# shield.net
KiCad netlist of a schematic drawn in EAGLE
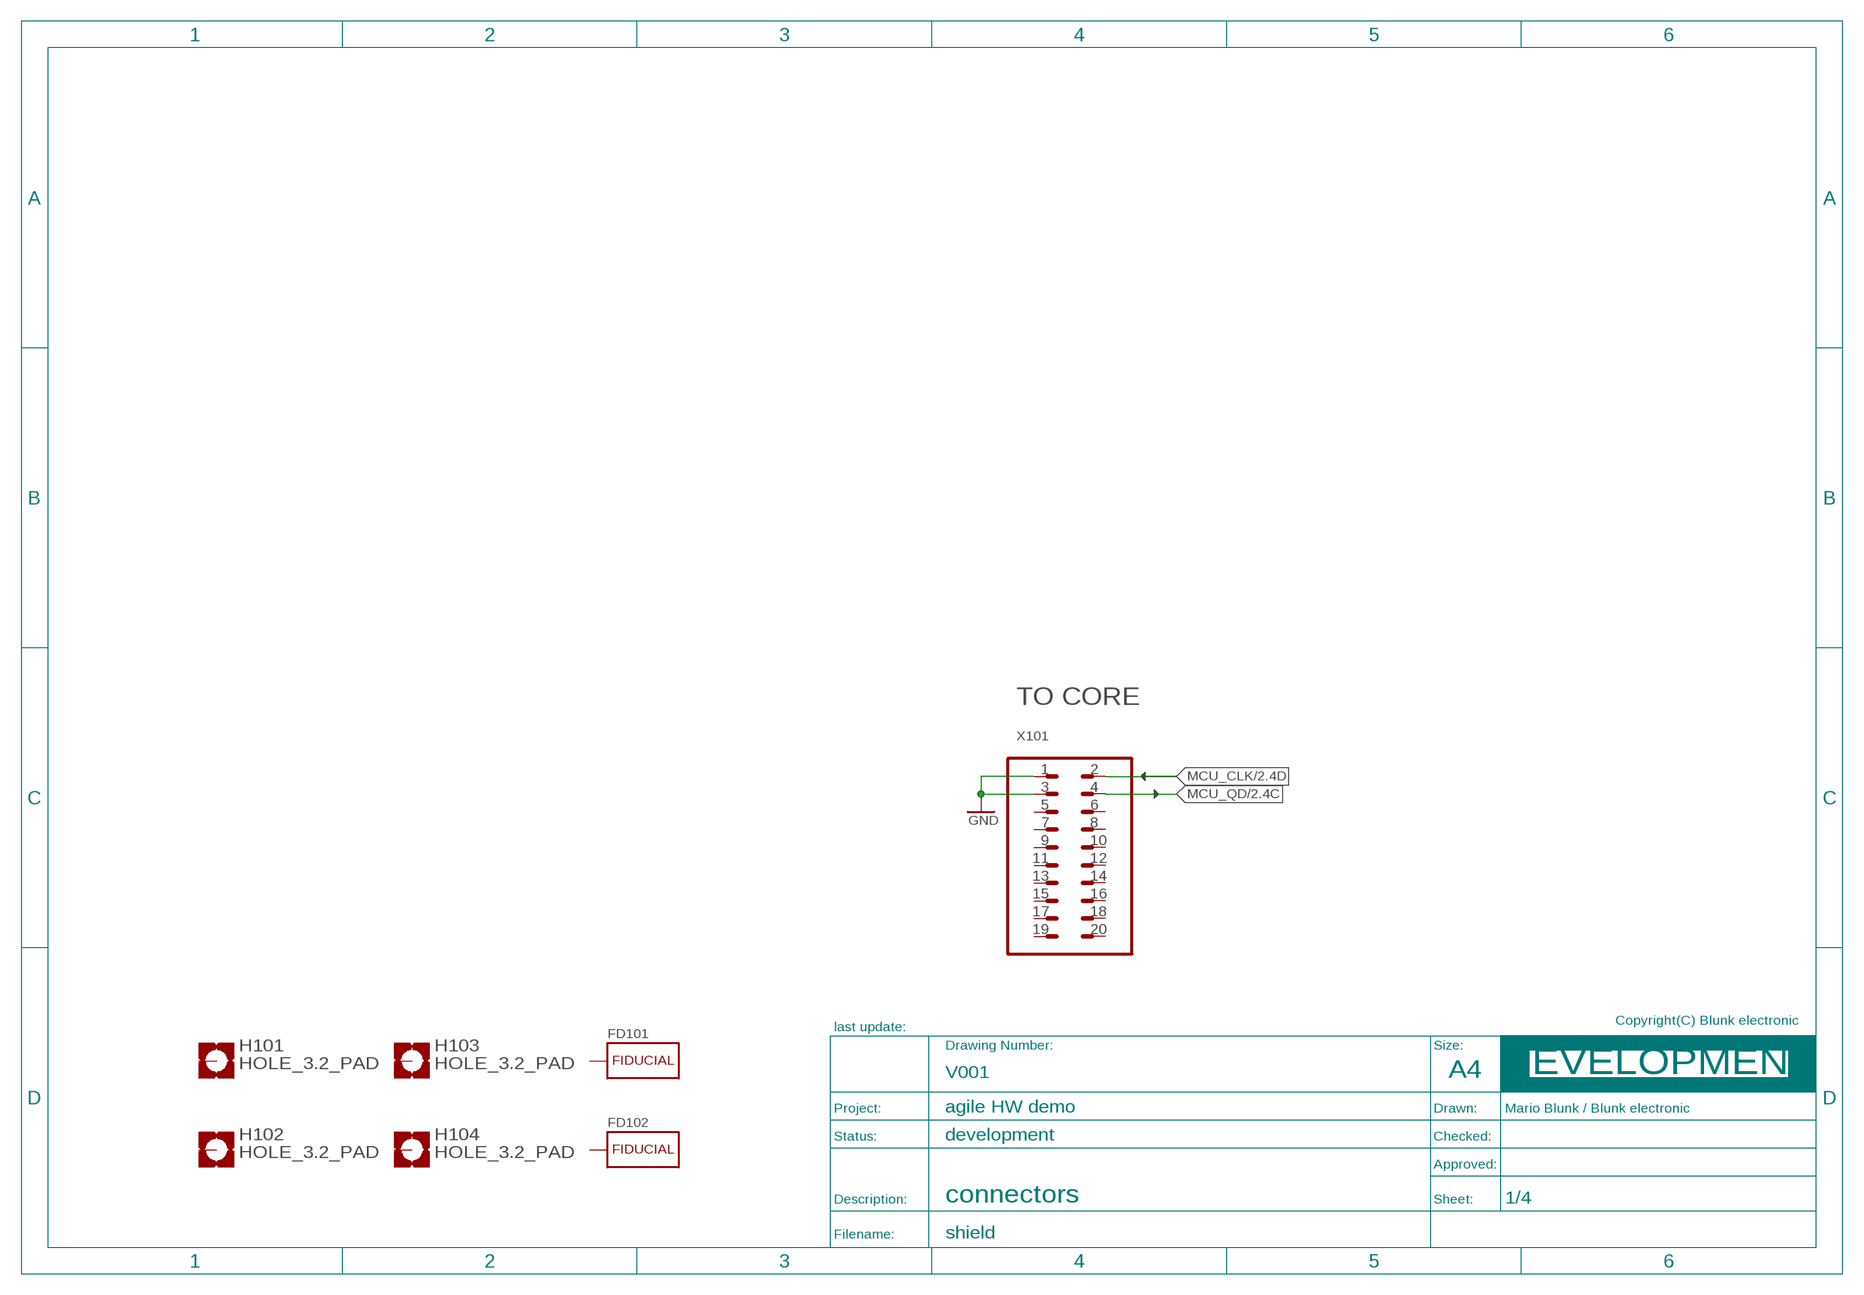
[diagram p0: schematic, sheet 1]
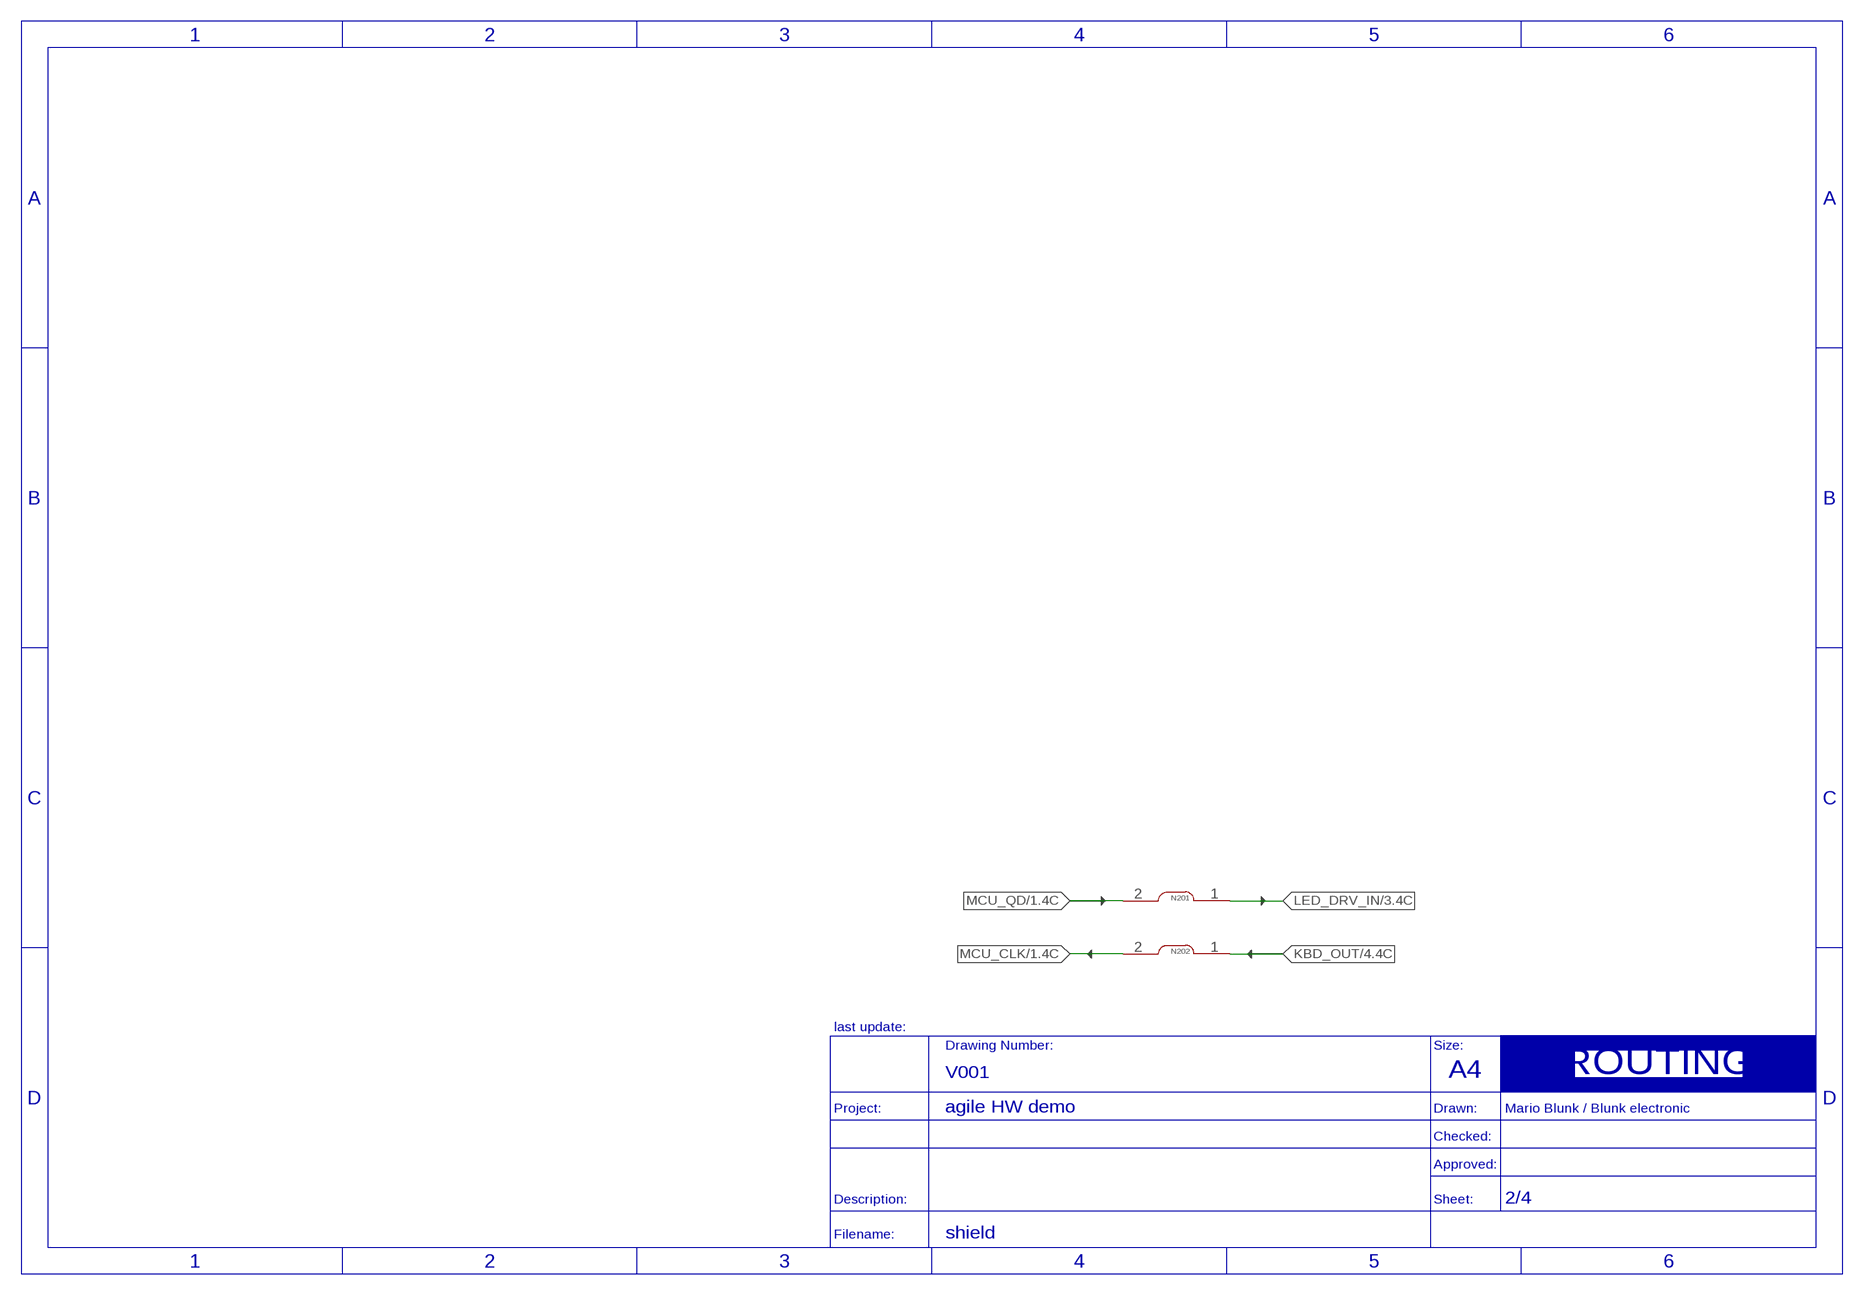
[diagram p1: schematic, sheet 2]
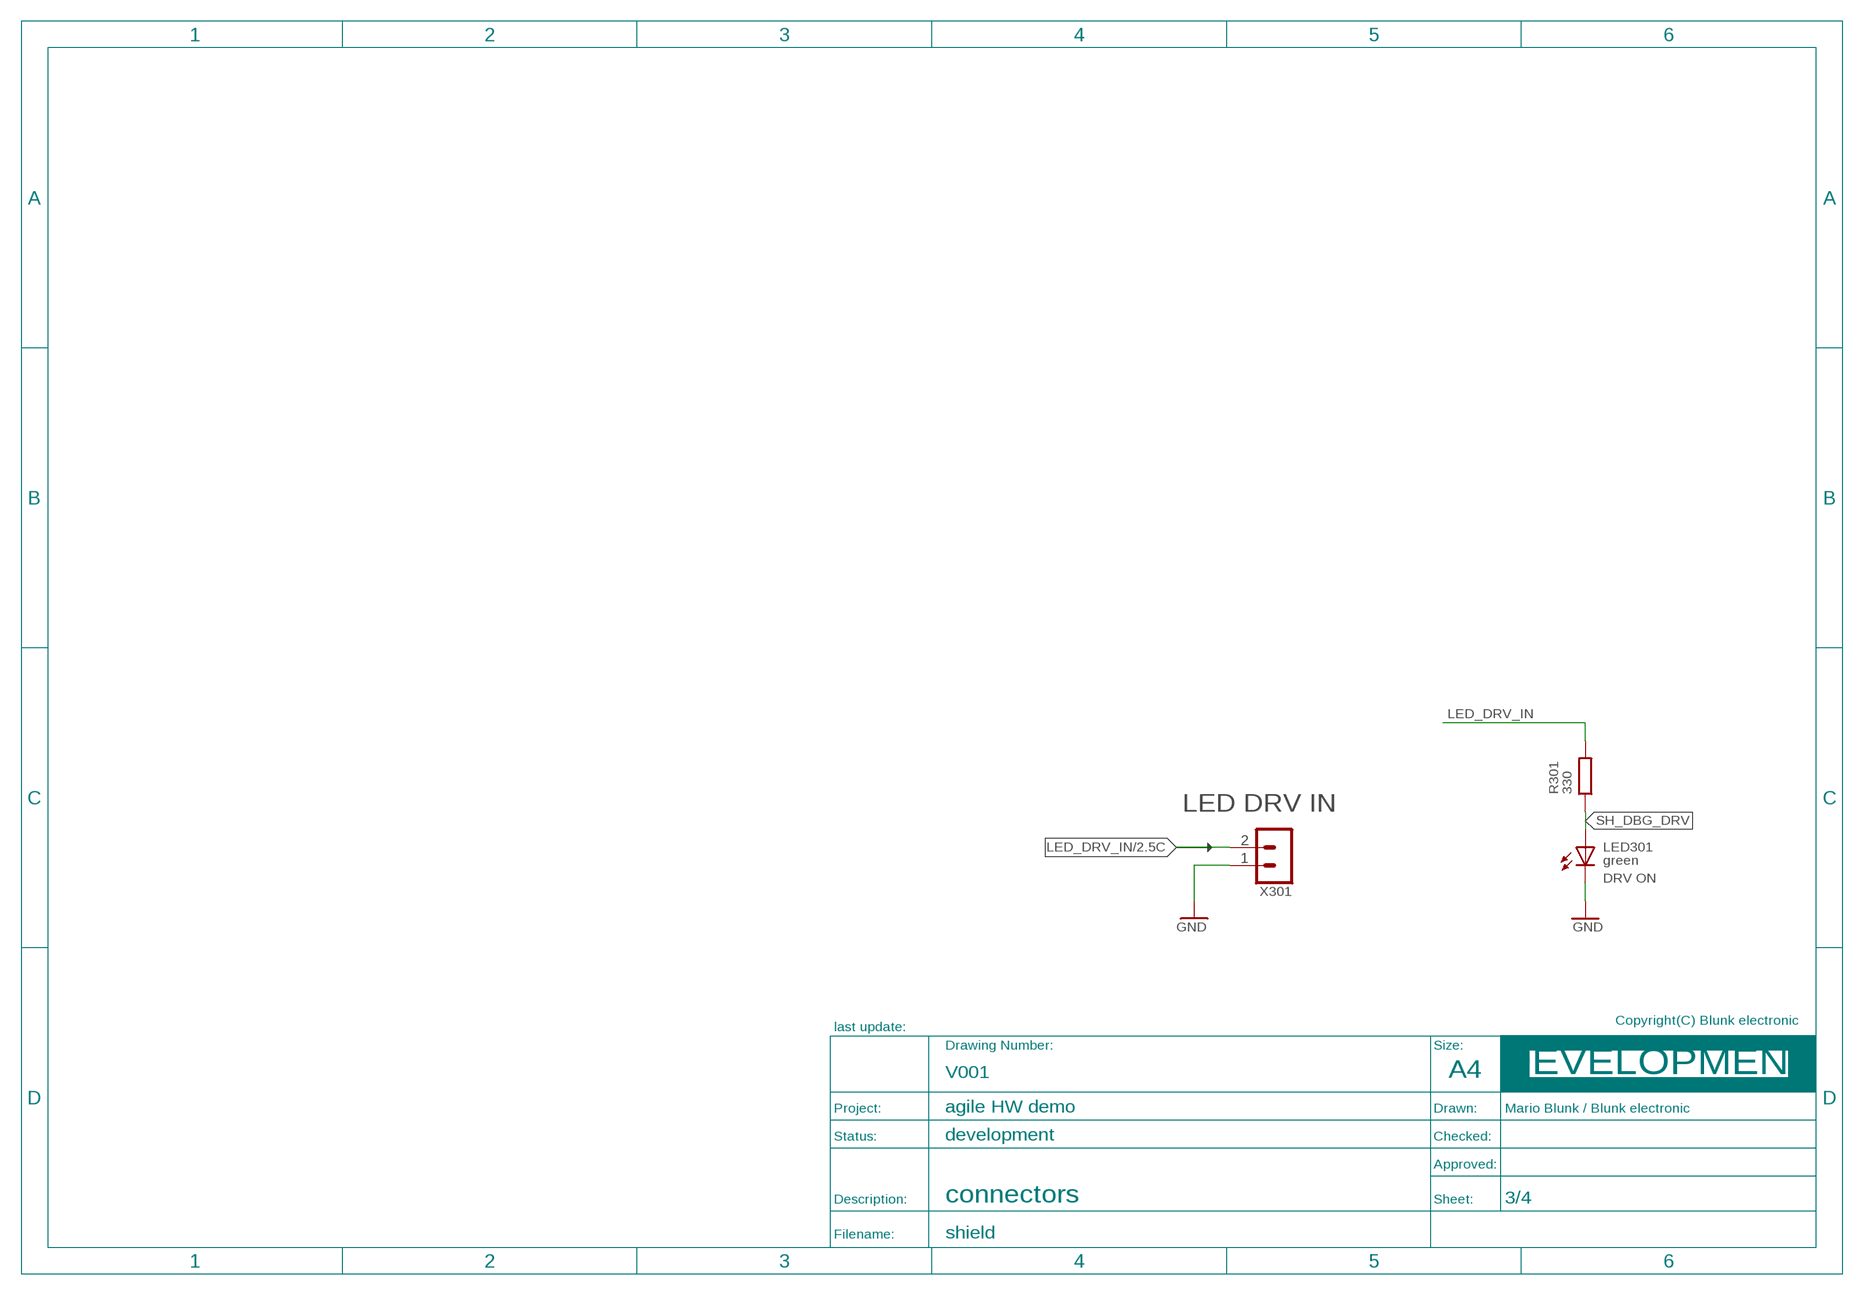
[diagram p2: schematic, sheet 3]
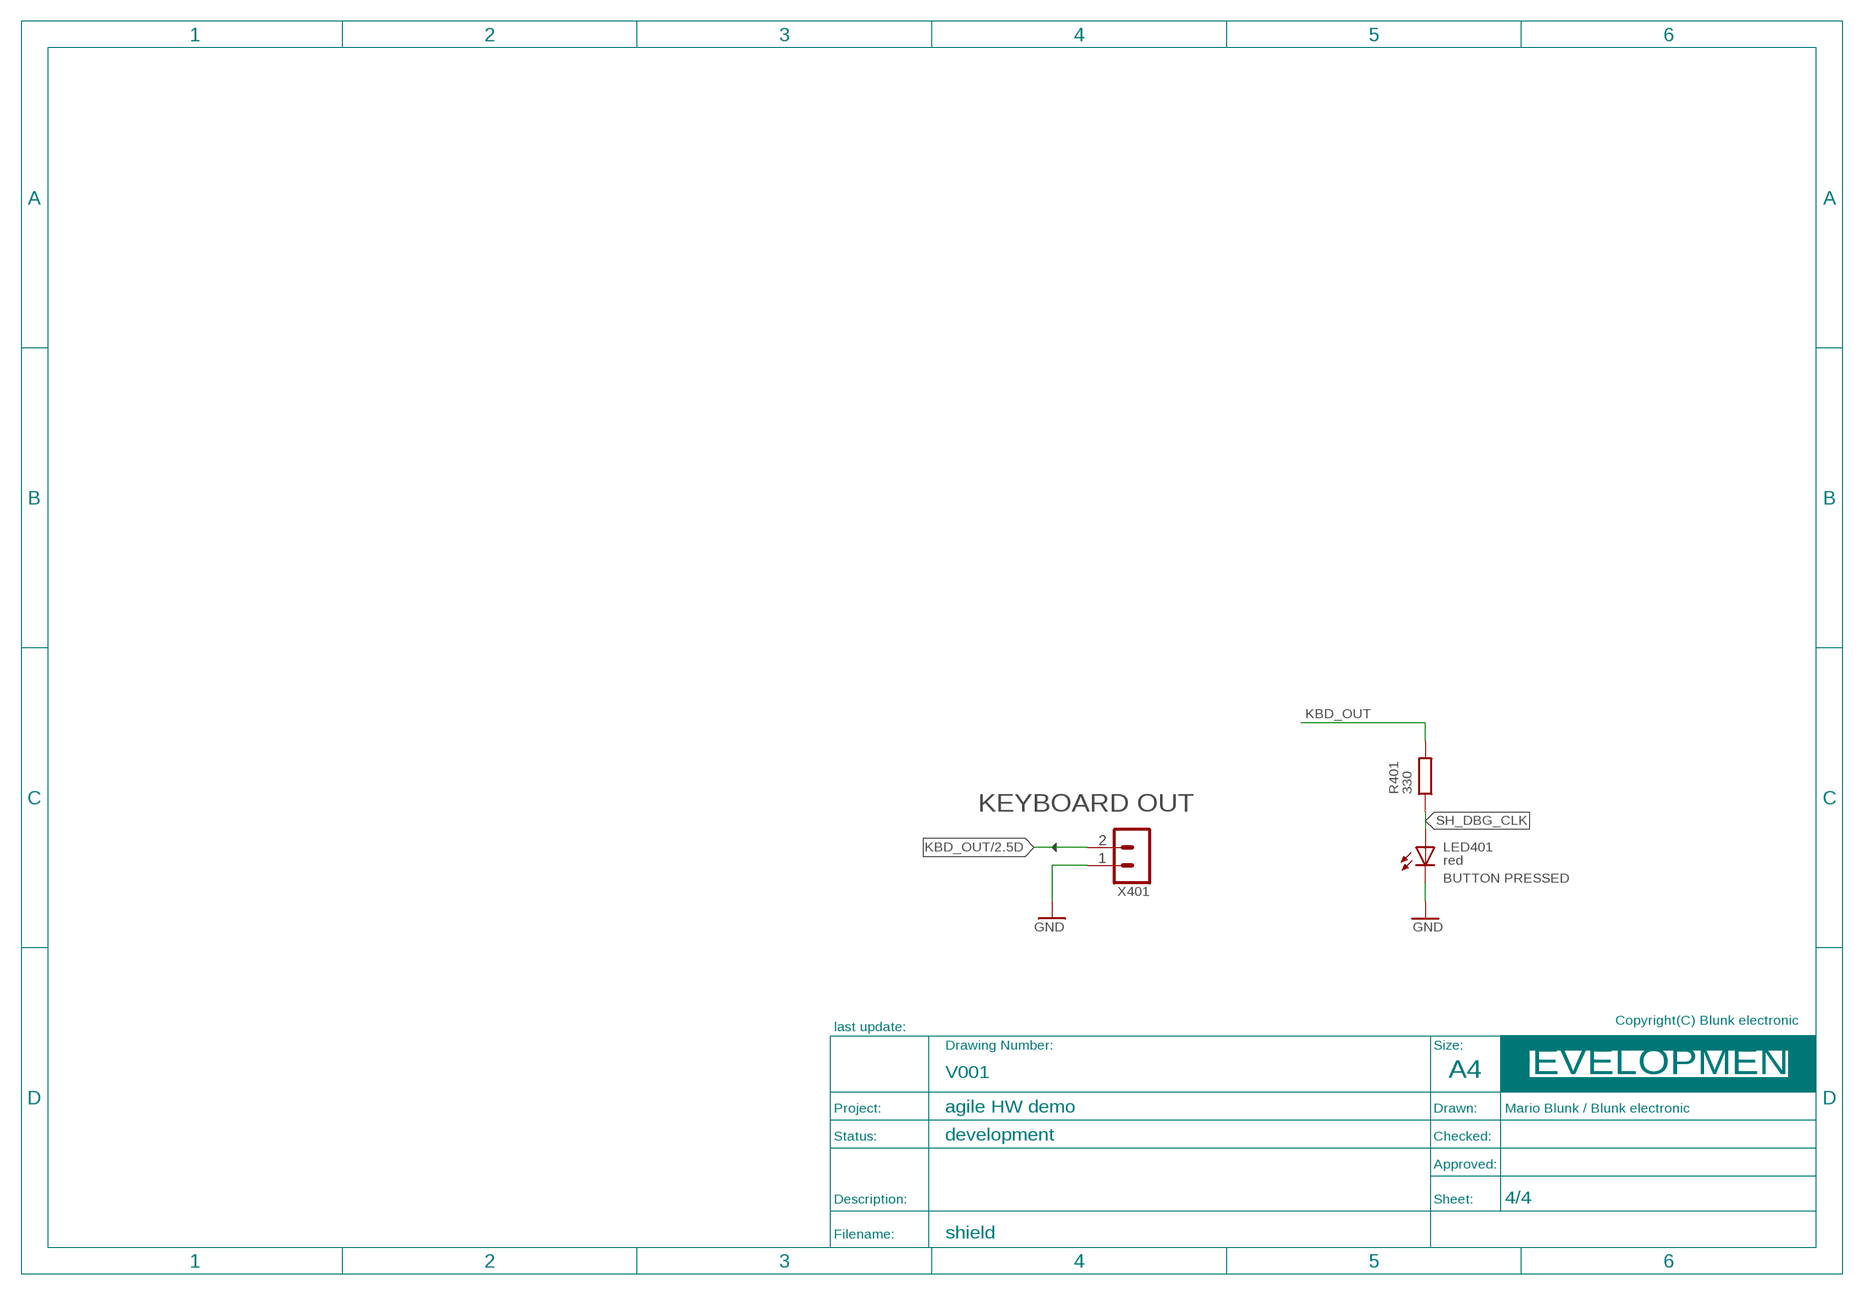
[diagram p3: schematic, sheet 4]

(export (version "E")
  (design (tool "Eeschema 10.0.6"))
  (components
    (comp (ref "N201")
      (value "NET_CHANGER-S-0.3MM")
      (footprint "eagle-import:S_NET_CHANGER_0.3MM")
      (libsource (lib "eagle-import") (part "NET_CHANGER-S-0.3MM"))
    )
    (comp (ref "N202")
      (value "NET_CHANGER-S-0.15MM")
      (footprint "eagle-import:S_NET_CHANGER_0.15MM")
      (libsource (lib "eagle-import") (part "NET_CHANGER-S-0.15MM"))
    )
    (comp (ref "LED301")
      (value "green")
      (footprint "eagle-import:S_0805")
      (fields (field (name "FUNCTION") "DRV ON") (field (name "PART_CODE_BEL") "LED_PAC_S_0805_VAL_green"))
      (libsource (lib "eagle-import") (part "LED_S_0805"))
    )
    (comp (ref "R301")
      (value "330")
      (footprint "eagle-import:S_0805")
      (fields (field (name "PART_CODE_BEL") "R_PAC_S_0805_VAL_330"))
      (libsource (lib "eagle-import") (part "R_S_0805"))
    )
    (comp (ref "X301")
      (value "MALE_2X1-T-VERTICAL")
      (footprint "eagle-import:T_MALE_2X1_VERTICAL_PITCH_2MM54")
      (fields (field (name "FUNCTION") "LED DRV IN"))
      (libsource (lib "eagle-import") (part "MALE_2X1-T-VERTICAL"))
    )
    (comp (ref "FD101")
      (value "FIDUCIAL_CROSSHAIR")
      (footprint "eagle-import:CROSSHAIR")
      (libsource (lib "eagle-import") (part "FIDUCIAL_CROSSHAIR"))
    )
    (comp (ref "FD102")
      (value "FIDUCIAL_CROSSHAIR")
      (footprint "eagle-import:CROSSHAIR")
      (libsource (lib "eagle-import") (part "FIDUCIAL_CROSSHAIR"))
    )
    (comp (ref "H101")
      (value "HOLE_3.2_PAD")
      (footprint "eagle-import:3.2_PAD")
      (libsource (lib "eagle-import") (part "HOLE_3.2_PAD"))
    )
    (comp (ref "H102")
      (value "HOLE_3.2_PAD")
      (footprint "eagle-import:3.2_PAD")
      (libsource (lib "eagle-import") (part "HOLE_3.2_PAD"))
    )
    (comp (ref "H103")
      (value "HOLE_3.2_PAD")
      (footprint "eagle-import:3.2_PAD")
      (libsource (lib "eagle-import") (part "HOLE_3.2_PAD"))
    )
    (comp (ref "H104")
      (value "HOLE_3.2_PAD")
      (footprint "eagle-import:3.2_PAD")
      (libsource (lib "eagle-import") (part "HOLE_3.2_PAD"))
    )
    (comp (ref "X101")
      (value "MALE_2X10-T-VERTICAL_2.54MM")
      (footprint "eagle-import:T_MALE_2X10_VERTICAL_GRID_2.54MM")
      (fields
        (field (name "FUNCTION") "TO CORE")
        (field (name "PART_CODE_BEL") "X_PAC_T_MALE_2X10_VERTICAL_PITCH_2mm54")
      )
      (libsource (lib "eagle-import") (part "MALE_2X10-T-VERTICAL_2.54MM"))
    )
    (comp (ref "LED401")
      (value "red")
      (footprint "eagle-import:S_0805")
      (fields
        (field (name "FUNCTION") "BUTTON PRESSED")
        (field (name "PART_CODE_BEL") "LED_PAC_S_0805_VAL_red")
      )
      (libsource (lib "eagle-import") (part "LED_S_0805"))
    )
    (comp (ref "R401")
      (value "330")
      (footprint "eagle-import:S_0805")
      (fields (field (name "PART_CODE_BEL") "R_PAC_S_0805_VAL_330"))
      (libsource (lib "eagle-import") (part "R_S_0805"))
    )
    (comp (ref "X401")
      (value "MALE_2X1-T-VERTICAL")
      (footprint "eagle-import:T_MALE_2X1_VERTICAL_PITCH_2MM54")
      (fields (field (name "FUNCTION") "KEYBOARD OUT"))
      (libsource (lib "eagle-import") (part "MALE_2X1-T-VERTICAL"))
    )
  )
  (nets
    (net (code "1") (name "GND") (class "Default")
      (node (ref "LED301") (pin "C") (pinfunction "C_C") (pintype "passive"))
      (node (ref "LED401") (pin "C") (pinfunction "C_C") (pintype "passive"))
      (node (ref "X101") (pin "1") (pinfunction "1_1") (pintype "passive"))
      (node (ref "X101") (pin "3") (pinfunction "3_3") (pintype "passive"))
      (node (ref "X301") (pin "1") (pinfunction "1_1") (pintype "passive"))
      (node (ref "X401") (pin "1") (pinfunction "1_1") (pintype "passive"))
    )
    (net (code "2") (name "KBD_OUT") (class "Default")
      (node (ref "N202") (pin "1") (pinfunction "1_1") (pintype "passive"))
      (node (ref "R401") (pin "2") (pinfunction "2_2") (pintype "passive"))
      (node (ref "X401") (pin "2") (pinfunction "2_2") (pintype "passive"))
    )
    (net (code "3") (name "LED_DRV_IN") (class "Default")
      (node (ref "N201") (pin "1") (pinfunction "1_1") (pintype "passive"))
      (node (ref "R301") (pin "2") (pinfunction "2_2") (pintype "passive"))
      (node (ref "X301") (pin "2") (pinfunction "2_2") (pintype "passive"))
    )
    (net (code "4") (name "MCU_CLK") (class "Default")
      (node (ref "N202") (pin "2") (pinfunction "2_2") (pintype "passive"))
      (node (ref "X101") (pin "2") (pinfunction "2_2") (pintype "passive"))
    )
    (net (code "5") (name "MCU_QD") (class "Default")
      (node (ref "N201") (pin "2") (pinfunction "2_2") (pintype "passive"))
      (node (ref "X101") (pin "4") (pinfunction "4_4") (pintype "passive"))
    )
    (net (code "6") (name "SH_DBG_CLK") (class "Default")
      (node (ref "LED401") (pin "A") (pinfunction "A_A") (pintype "passive"))
      (node (ref "R401") (pin "1") (pinfunction "1_1") (pintype "passive"))
    )
    (net (code "7") (name "SH_DBG_DRV") (class "Default")
      (node (ref "LED301") (pin "A") (pinfunction "A_A") (pintype "passive"))
      (node (ref "R301") (pin "1") (pinfunction "1_1") (pintype "passive"))
    )
    (net (code "8") (name "unconnected-(FD101-NC-Pad1)") (class "Default")
      (node (ref "FD101") (pin "1") (pinfunction "NC_1") (pintype "no_connect"))
    )
    (net (code "9") (name "unconnected-(FD102-NC-Pad1)") (class "Default")
      (node (ref "FD102") (pin "1") (pinfunction "NC_1") (pintype "no_connect"))
    )
    (net (code "10") (name "unconnected-(H101-MOUNT-PadH1)") (class "Default")
      (node (ref "H101") (pin "H1") (pinfunction "MOUNT_H1") (pintype "passive"))
    )
    (net (code "11") (name "unconnected-(H102-MOUNT-PadH1)") (class "Default")
      (node (ref "H102") (pin "H1") (pinfunction "MOUNT_H1") (pintype "passive"))
    )
    (net (code "12") (name "unconnected-(H103-MOUNT-PadH1)") (class "Default")
      (node (ref "H103") (pin "H1") (pinfunction "MOUNT_H1") (pintype "passive"))
    )
    (net (code "13") (name "unconnected-(H104-MOUNT-PadH1)") (class "Default")
      (node (ref "H104") (pin "H1") (pinfunction "MOUNT_H1") (pintype "passive"))
    )
    (net (code "14") (name "unconnected-(X101-Pad5)") (class "Default")
      (node (ref "X101") (pin "5") (pinfunction "5_5") (pintype "passive"))
    )
    (net (code "15") (name "unconnected-(X101-Pad6)") (class "Default")
      (node (ref "X101") (pin "6") (pinfunction "6_6") (pintype "passive"))
    )
    (net (code "16") (name "unconnected-(X101-Pad7)") (class "Default")
      (node (ref "X101") (pin "7") (pinfunction "7_7") (pintype "passive"))
    )
    (net (code "17") (name "unconnected-(X101-Pad8)") (class "Default")
      (node (ref "X101") (pin "8") (pinfunction "8_8") (pintype "passive"))
    )
    (net (code "18") (name "unconnected-(X101-Pad9)") (class "Default")
      (node (ref "X101") (pin "9") (pinfunction "9_9") (pintype "passive"))
    )
    (net (code "19") (name "unconnected-(X101-Pad10)") (class "Default")
      (node (ref "X101") (pin "10") (pinfunction "10_10") (pintype "passive"))
    )
    (net (code "20") (name "unconnected-(X101-Pad11)") (class "Default")
      (node (ref "X101") (pin "11") (pinfunction "11_11") (pintype "passive"))
    )
    (net (code "21") (name "unconnected-(X101-Pad12)") (class "Default")
      (node (ref "X101") (pin "12") (pinfunction "12_12") (pintype "passive"))
    )
    (net (code "22") (name "unconnected-(X101-Pad13)") (class "Default")
      (node (ref "X101") (pin "13") (pinfunction "13_13") (pintype "passive"))
    )
    (net (code "23") (name "unconnected-(X101-Pad14)") (class "Default")
      (node (ref "X101") (pin "14") (pinfunction "14_14") (pintype "passive"))
    )
    (net (code "24") (name "unconnected-(X101-Pad15)") (class "Default")
      (node (ref "X101") (pin "15") (pinfunction "15_15") (pintype "passive"))
    )
    (net (code "25") (name "unconnected-(X101-Pad16)") (class "Default")
      (node (ref "X101") (pin "16") (pinfunction "16_16") (pintype "passive"))
    )
    (net (code "26") (name "unconnected-(X101-Pad17)") (class "Default")
      (node (ref "X101") (pin "17") (pinfunction "17_17") (pintype "passive"))
    )
    (net (code "27") (name "unconnected-(X101-Pad18)") (class "Default")
      (node (ref "X101") (pin "18") (pinfunction "18_18") (pintype "passive"))
    )
    (net (code "28") (name "unconnected-(X101-Pad19)") (class "Default")
      (node (ref "X101") (pin "19") (pinfunction "19_19") (pintype "passive"))
    )
    (net (code "29") (name "unconnected-(X101-Pad20)") (class "Default")
      (node (ref "X101") (pin "20") (pinfunction "20_20") (pintype "passive"))
    )
  )
)
